# 3DP-GLCD.net
KiCad netlist of a schematic drawn in Altium Designer
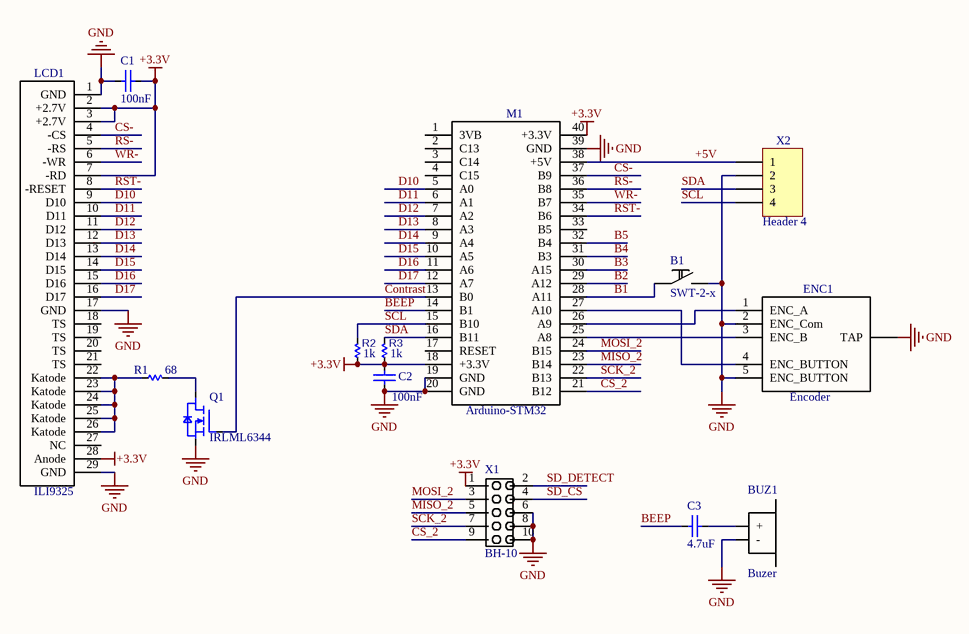
[diagram p0: 3DP-GLCD.SchDoc]

(export (version "E")
  (design (tool "Eeschema 10.0.6"))
  (components
    (comp (ref "B1") (value "SWT-2-x") (footprint "SWT-2-x") (libsource (lib "My_Schlib") (part "SWT-2-x")))
    (comp (ref "BUZ1") (value "Buzer") (footprint "Buzer_12xx") (libsource (lib "My_Schlib") (part "Buzer")))
    (comp (ref "C1")
      (value "100nF")
      (footprint "C0805_Murata")
      (fields
        (field (name "PART NUMBER") "GRM21BR71H104KA01L")
        (field (name "VOLTAGE") "50V")
        (field (name "TOLERANCE") "10 %")
      )
      (libsource (lib "CorpLib") (part "Cap"))
    )
    (comp (ref "C2")
      (value "100nF")
      (footprint "C0805_Murata")
      (fields
        (field (name "PART NUMBER") "GRM21BR71H104KA01L")
        (field (name "VOLTAGE") "50V")
        (field (name "TOLERANCE") "10 %")
      )
      (libsource (lib "CorpLib") (part "Cap"))
    )
    (comp (ref "C3")
      (value "4.7uF")
      (footprint "C1206_Murata")
      (fields
        (field (name "PART NUMBER") "GRM31CR71H475KA12L")
        (field (name "VOLTAGE") "50V")
        (field (name "TOLERANCE") "10 %")
      )
      (libsource (lib "CorpLib") (part "Cap"))
    )
    (comp (ref "ENC1")
      (value "Encoder")
      (footprint "Encoder_bot")
      (description "Rotary Encoder with button")
      (libsource (lib "My_Schlib") (part "Encoder"))
    )
    (comp (ref "LCD1")
      (value "ILI9325")
      (footprint "LCD-ILI9325-29pin-top")
      (description "TFT LCD")
      (libsource (lib "My_Schlib") (part "LCD-ILI9325-29pin"))
    )
    (comp (ref "M1")
      (value "Arduino-STM32")
      (footprint "ARDUINO-STM32")
      (libsource (lib "My_Schlib") (part "ARDUINO-STM32"))
    )
    (comp (ref "Q1")
      (value "IRLML6344")
      (footprint "SOT23-3_IR")
      (description "30 V, 5.0 A, 0.029 Ohm Single N-Channel HEXFET Power MOSFET")
      (fields
        (field (name "PART NUMBER") "IRLML6344TRPBF")
        (field (name "PART LABEL") "IRLML6344")
        (field (name "MANUFACTURER") "International Rectifier")
      )
      (libsource (lib "CorpLib") (part "IRLML6344"))
    )
    (comp (ref "R1")
      (value "68")
      (footprint "R0805_UniOhm")
      (fields
        (field (name "PART NUMBER") "0805S8F4700T50")
        (field (name "TOLERANCE") "1 %")
        (field (name "MANUFACTURER") "uniOhm")
      )
      (libsource (lib "CorpLib") (part "R"))
    )
    (comp (ref "R2")
      (value "1k")
      (footprint "R0805_UniOhm")
      (description "Resistor")
      (fields (field (name "Comment") "R"))
      (libsource (lib "Passive") (part "R"))
    )
    (comp (ref "R3")
      (value "1k")
      (footprint "R0805_UniOhm")
      (description "Resistor")
      (fields (field (name "Comment") "R"))
      (libsource (lib "Passive") (part "R"))
    )
    (comp (ref "X1") (value "BH-10") (footprint "BH-10") (libsource (lib "My_Schlib") (part "BH-10_2")))
    (comp (ref "X2")
      (value "Header 4")
      (footprint "HDR1X4")
      (description "Header, 4-Pin")
      (fields (field (name "PUBLISHER") "Altium Limited"))
      (libsource (lib "Miscellaneous Connectors") (part "Header 4"))
    )
  )
  (nets
    (net (code "1") (name "+3.3V") (class "Default")
      (node (ref "C1") (pin "1") (pinfunction "1_1") (pintype "passive"))
      (node (ref "C2") (pin "1") (pinfunction "1_1") (pintype "passive"))
      (node (ref "LCD1") (pin "2") (pinfunction "+2.7V_2") (pintype "passive"))
      (node (ref "LCD1") (pin "28") (pinfunction "Anode_28") (pintype "passive"))
      (node (ref "LCD1") (pin "3") (pinfunction "+2.7V_3") (pintype "passive"))
      (node (ref "LCD1") (pin "7") (pinfunction "-RD_7") (pintype "passive"))
      (node (ref "M1") (pin "18") (pinfunction "+3.3V_18") (pintype "passive"))
      (node (ref "M1") (pin "40") (pinfunction "+3.3V_40") (pintype "passive"))
      (node (ref "R2") (pin "1") (pinfunction "1_1") (pintype "passive"))
      (node (ref "R3") (pin "1") (pinfunction "1_1") (pintype "passive"))
      (node (ref "X1") (pin "1") (pinfunction "1_1") (pintype "passive"))
    )
    (net (code "2") (name "/+5V") (class "Default")
      (node (ref "M1") (pin "38") (pinfunction "+5V_38") (pintype "passive"))
      (node (ref "X2") (pin "1") (pinfunction "1_1") (pintype "passive"))
    )
    (net (code "3") (name "/B1") (class "Default")
      (node (ref "B1") (pin "1") (pinfunction "1_1") (pintype "passive"))
      (node (ref "M1") (pin "28") (pinfunction "A11_28") (pintype "passive"))
    )
    (net (code "4") (name "/B2") (class "Default")
      (node (ref "M1") (pin "29") (pinfunction "A12_29") (pintype "passive"))
    )
    (net (code "5") (name "/B3") (class "Default")
      (node (ref "M1") (pin "30") (pinfunction "A15_30") (pintype "passive"))
    )
    (net (code "6") (name "/B4") (class "Default")
      (node (ref "M1") (pin "31") (pinfunction "B3_31") (pintype "passive"))
    )
    (net (code "7") (name "/B5") (class "Default")
      (node (ref "M1") (pin "32") (pinfunction "B4_32") (pintype "passive"))
    )
    (net (code "8") (name "/BEEP") (class "Default")
      (node (ref "C3") (pin "1") (pinfunction "1_1") (pintype "passive"))
      (node (ref "M1") (pin "14") (pinfunction "B1_14") (pintype "passive"))
    )
    (net (code "9") (name "/CS-") (class "Default")
      (node (ref "LCD1") (pin "4") (pinfunction "-CS_4") (pintype "passive"))
      (node (ref "M1") (pin "37") (pinfunction "B9_37") (pintype "passive"))
    )
    (net (code "10") (name "/CS_2") (class "Default")
      (node (ref "M1") (pin "21") (pinfunction "B12_21") (pintype "passive"))
      (node (ref "X1") (pin "9") (pinfunction "9_9") (pintype "passive"))
    )
    (net (code "11") (name "/Contrast") (class "Default")
      (node (ref "M1") (pin "13") (pinfunction "B0_13") (pintype "passive"))
      (node (ref "Q1") (pin "1") (pinfunction "G_1") (pintype "passive"))
    )
    (net (code "12") (name "/D10") (class "Default")
      (node (ref "LCD1") (pin "9") (pinfunction "D10_9") (pintype "passive"))
      (node (ref "M1") (pin "5") (pinfunction "A0_5") (pintype "passive"))
    )
    (net (code "13") (name "/D11") (class "Default")
      (node (ref "LCD1") (pin "10") (pinfunction "D11_10") (pintype "passive"))
      (node (ref "M1") (pin "6") (pinfunction "A1_6") (pintype "passive"))
    )
    (net (code "14") (name "/D12") (class "Default")
      (node (ref "LCD1") (pin "11") (pinfunction "D12_11") (pintype "passive"))
      (node (ref "M1") (pin "7") (pinfunction "A2_7") (pintype "passive"))
    )
    (net (code "15") (name "/D13") (class "Default")
      (node (ref "LCD1") (pin "12") (pinfunction "D13_12") (pintype "passive"))
      (node (ref "M1") (pin "8") (pinfunction "A3_8") (pintype "passive"))
    )
    (net (code "16") (name "/D14") (class "Default")
      (node (ref "LCD1") (pin "13") (pinfunction "D14_13") (pintype "passive"))
      (node (ref "M1") (pin "9") (pinfunction "A4_9") (pintype "passive"))
    )
    (net (code "17") (name "/D15") (class "Default")
      (node (ref "LCD1") (pin "14") (pinfunction "D15_14") (pintype "passive"))
      (node (ref "M1") (pin "10") (pinfunction "A5_10") (pintype "passive"))
    )
    (net (code "18") (name "/D16") (class "Default")
      (node (ref "LCD1") (pin "15") (pinfunction "D16_15") (pintype "passive"))
      (node (ref "M1") (pin "11") (pinfunction "A6_11") (pintype "passive"))
    )
    (net (code "19") (name "/D17") (class "Default")
      (node (ref "LCD1") (pin "16") (pinfunction "D17_16") (pintype "passive"))
      (node (ref "M1") (pin "12") (pinfunction "A7_12") (pintype "passive"))
    )
    (net (code "20") (name "/MISO_2") (class "Default")
      (node (ref "M1") (pin "23") (pinfunction "B14_23") (pintype "passive"))
      (node (ref "X1") (pin "5") (pinfunction "5_5") (pintype "passive"))
    )
    (net (code "21") (name "/MOSI_2") (class "Default")
      (node (ref "M1") (pin "24") (pinfunction "B15_24") (pintype "passive"))
      (node (ref "X1") (pin "3") (pinfunction "3_3") (pintype "passive"))
    )
    (net (code "22") (name "/RS-") (class "Default")
      (node (ref "LCD1") (pin "5") (pinfunction "-RS_5") (pintype "passive"))
      (node (ref "M1") (pin "36") (pinfunction "B8_36") (pintype "passive"))
    )
    (net (code "23") (name "/RST-") (class "Default")
      (node (ref "LCD1") (pin "8") (pinfunction "-RESET_8") (pintype "passive"))
      (node (ref "M1") (pin "34") (pinfunction "B6_34") (pintype "passive"))
    )
    (net (code "24") (name "/SCK_2") (class "Default")
      (node (ref "M1") (pin "22") (pinfunction "B13_22") (pintype "passive"))
      (node (ref "X1") (pin "7") (pinfunction "7_7") (pintype "passive"))
    )
    (net (code "25") (name "/SCL") (class "Default")
      (node (ref "M1") (pin "15") (pinfunction "B10_15") (pintype "passive"))
      (node (ref "R2") (pin "2") (pinfunction "2_2") (pintype "passive"))
      (node (ref "X2") (pin "4") (pinfunction "4_4") (pintype "passive"))
    )
    (net (code "26") (name "/SDA") (class "Default")
      (node (ref "M1") (pin "16") (pinfunction "B11_16") (pintype "passive"))
      (node (ref "R3") (pin "2") (pinfunction "2_2") (pintype "passive"))
      (node (ref "X2") (pin "3") (pinfunction "3_3") (pintype "passive"))
    )
    (net (code "27") (name "/SD_CS") (class "Default")
      (node (ref "X1") (pin "4") (pinfunction "4_4") (pintype "passive"))
    )
    (net (code "28") (name "/SD_DETECT") (class "Default")
      (node (ref "X1") (pin "2") (pinfunction "2_2") (pintype "passive"))
    )
    (net (code "29") (name "/WR-") (class "Default")
      (node (ref "LCD1") (pin "6") (pinfunction "-WR_6") (pintype "passive"))
      (node (ref "M1") (pin "35") (pinfunction "B7_35") (pintype "passive"))
    )
    (net (code "30") (name "GND") (class "Default")
      (node (ref "B1") (pin "2") (pinfunction "2_2") (pintype "passive"))
      (node (ref "BUZ1") (pin "2") (pinfunction "-_2") (pintype "passive"))
      (node (ref "C1") (pin "2") (pinfunction "2_2") (pintype "passive"))
      (node (ref "C2") (pin "2") (pinfunction "2_2") (pintype "passive"))
      (node (ref "ENC1") (pin "0") (pinfunction "TAP_0") (pintype "passive"))
      (node (ref "ENC1") (pin "2") (pinfunction "ENC_Com_2") (pintype "passive"))
      (node (ref "ENC1") (pin "5") (pinfunction "ENC_BUTTON_5") (pintype "passive"))
      (node (ref "LCD1") (pin "1") (pinfunction "GND_1") (pintype "passive"))
      (node (ref "LCD1") (pin "17") (pinfunction "GND_17") (pintype "passive"))
      (node (ref "LCD1") (pin "29") (pinfunction "GND_29") (pintype "passive"))
      (node (ref "M1") (pin "19") (pinfunction "GND_19") (pintype "passive"))
      (node (ref "M1") (pin "20") (pinfunction "GND_20") (pintype "passive"))
      (node (ref "M1") (pin "39") (pinfunction "GND_39") (pintype "passive"))
      (node (ref "Q1") (pin "2") (pinfunction "S_2") (pintype "passive"))
      (node (ref "X1") (pin "10") (pinfunction "10_10") (pintype "passive"))
      (node (ref "X1") (pin "6") (pinfunction "6_6") (pintype "passive"))
      (node (ref "X1") (pin "8") (pinfunction "8_8") (pintype "passive"))
      (node (ref "X2") (pin "2") (pinfunction "2_2") (pintype "passive"))
    )
    (net (code "31") (name "Net-(BUZ1-+)") (class "Default")
      (node (ref "BUZ1") (pin "1") (pinfunction "+_1") (pintype "passive"))
      (node (ref "C3") (pin "2") (pinfunction "2_2") (pintype "passive"))
    )
    (net (code "32") (name "Net-(ENC1-ENC_A)") (class "Default")
      (node (ref "ENC1") (pin "1") (pinfunction "ENC_A_1") (pintype "passive"))
      (node (ref "M1") (pin "26") (pinfunction "A9_26") (pintype "passive"))
    )
    (net (code "33") (name "Net-(ENC1-ENC_B)") (class "Default")
      (node (ref "ENC1") (pin "3") (pinfunction "ENC_B_3") (pintype "passive"))
      (node (ref "M1") (pin "25") (pinfunction "A8_25") (pintype "passive"))
    )
    (net (code "34") (name "Net-(LCD1-Katode-Pad22)") (class "Default")
      (node (ref "LCD1") (pin "22") (pinfunction "Katode_22") (pintype "passive"))
      (node (ref "LCD1") (pin "23") (pinfunction "Katode_23") (pintype "passive"))
      (node (ref "LCD1") (pin "24") (pinfunction "Katode_24") (pintype "passive"))
      (node (ref "LCD1") (pin "25") (pinfunction "Katode_25") (pintype "passive"))
      (node (ref "LCD1") (pin "26") (pinfunction "Katode_26") (pintype "passive"))
      (node (ref "R1") (pin "1") (pinfunction "1_1") (pintype "passive"))
    )
    (net (code "35") (name "Net-(M1-A10)") (class "Default")
      (node (ref "ENC1") (pin "4") (pinfunction "ENC_BUTTON_4") (pintype "passive"))
      (node (ref "M1") (pin "27") (pinfunction "A10_27") (pintype "passive"))
    )
    (net (code "36") (name "Net-(Q1-D)") (class "Default")
      (node (ref "Q1") (pin "3") (pinfunction "D_3") (pintype "passive"))
      (node (ref "R1") (pin "2") (pinfunction "2_2") (pintype "passive"))
    )
    (net (code "37") (name "unconnected-(LCD1-NC-Pad27)") (class "Default")
      (node (ref "LCD1") (pin "27") (pinfunction "NC_27") (pintype "passive"))
    )
    (net (code "38") (name "unconnected-(LCD1-TS-Pad18)") (class "Default")
      (node (ref "LCD1") (pin "18") (pinfunction "TS_18") (pintype "passive"))
    )
    (net (code "39") (name "unconnected-(LCD1-TS-Pad19)") (class "Default")
      (node (ref "LCD1") (pin "19") (pinfunction "TS_19") (pintype "passive"))
    )
    (net (code "40") (name "unconnected-(LCD1-TS-Pad20)") (class "Default")
      (node (ref "LCD1") (pin "20") (pinfunction "TS_20") (pintype "passive"))
    )
    (net (code "41") (name "unconnected-(LCD1-TS-Pad21)") (class "Default")
      (node (ref "LCD1") (pin "21") (pinfunction "TS_21") (pintype "passive"))
    )
    (net (code "42") (name "unconnected-(M1-3VB-Pad1)") (class "Default")
      (node (ref "M1") (pin "1") (pinfunction "3VB_1") (pintype "passive"))
    )
    (net (code "43") (name "unconnected-(M1-B5-Pad33)") (class "Default")
      (node (ref "M1") (pin "33") (pinfunction "B5_33") (pintype "passive"))
    )
    (net (code "44") (name "unconnected-(M1-C13-Pad2)") (class "Default")
      (node (ref "M1") (pin "2") (pinfunction "C13_2") (pintype "passive"))
    )
    (net (code "45") (name "unconnected-(M1-C14-Pad3)") (class "Default")
      (node (ref "M1") (pin "3") (pinfunction "C14_3") (pintype "passive"))
    )
    (net (code "46") (name "unconnected-(M1-C15-Pad4)") (class "Default")
      (node (ref "M1") (pin "4") (pinfunction "C15_4") (pintype "passive"))
    )
    (net (code "47") (name "unconnected-(M1-RESET-Pad17)") (class "Default")
      (node (ref "M1") (pin "17") (pinfunction "RESET_17") (pintype "passive"))
    )
  )
)
